# Display.net
KiCad netlist of a schematic drawn in EAGLE
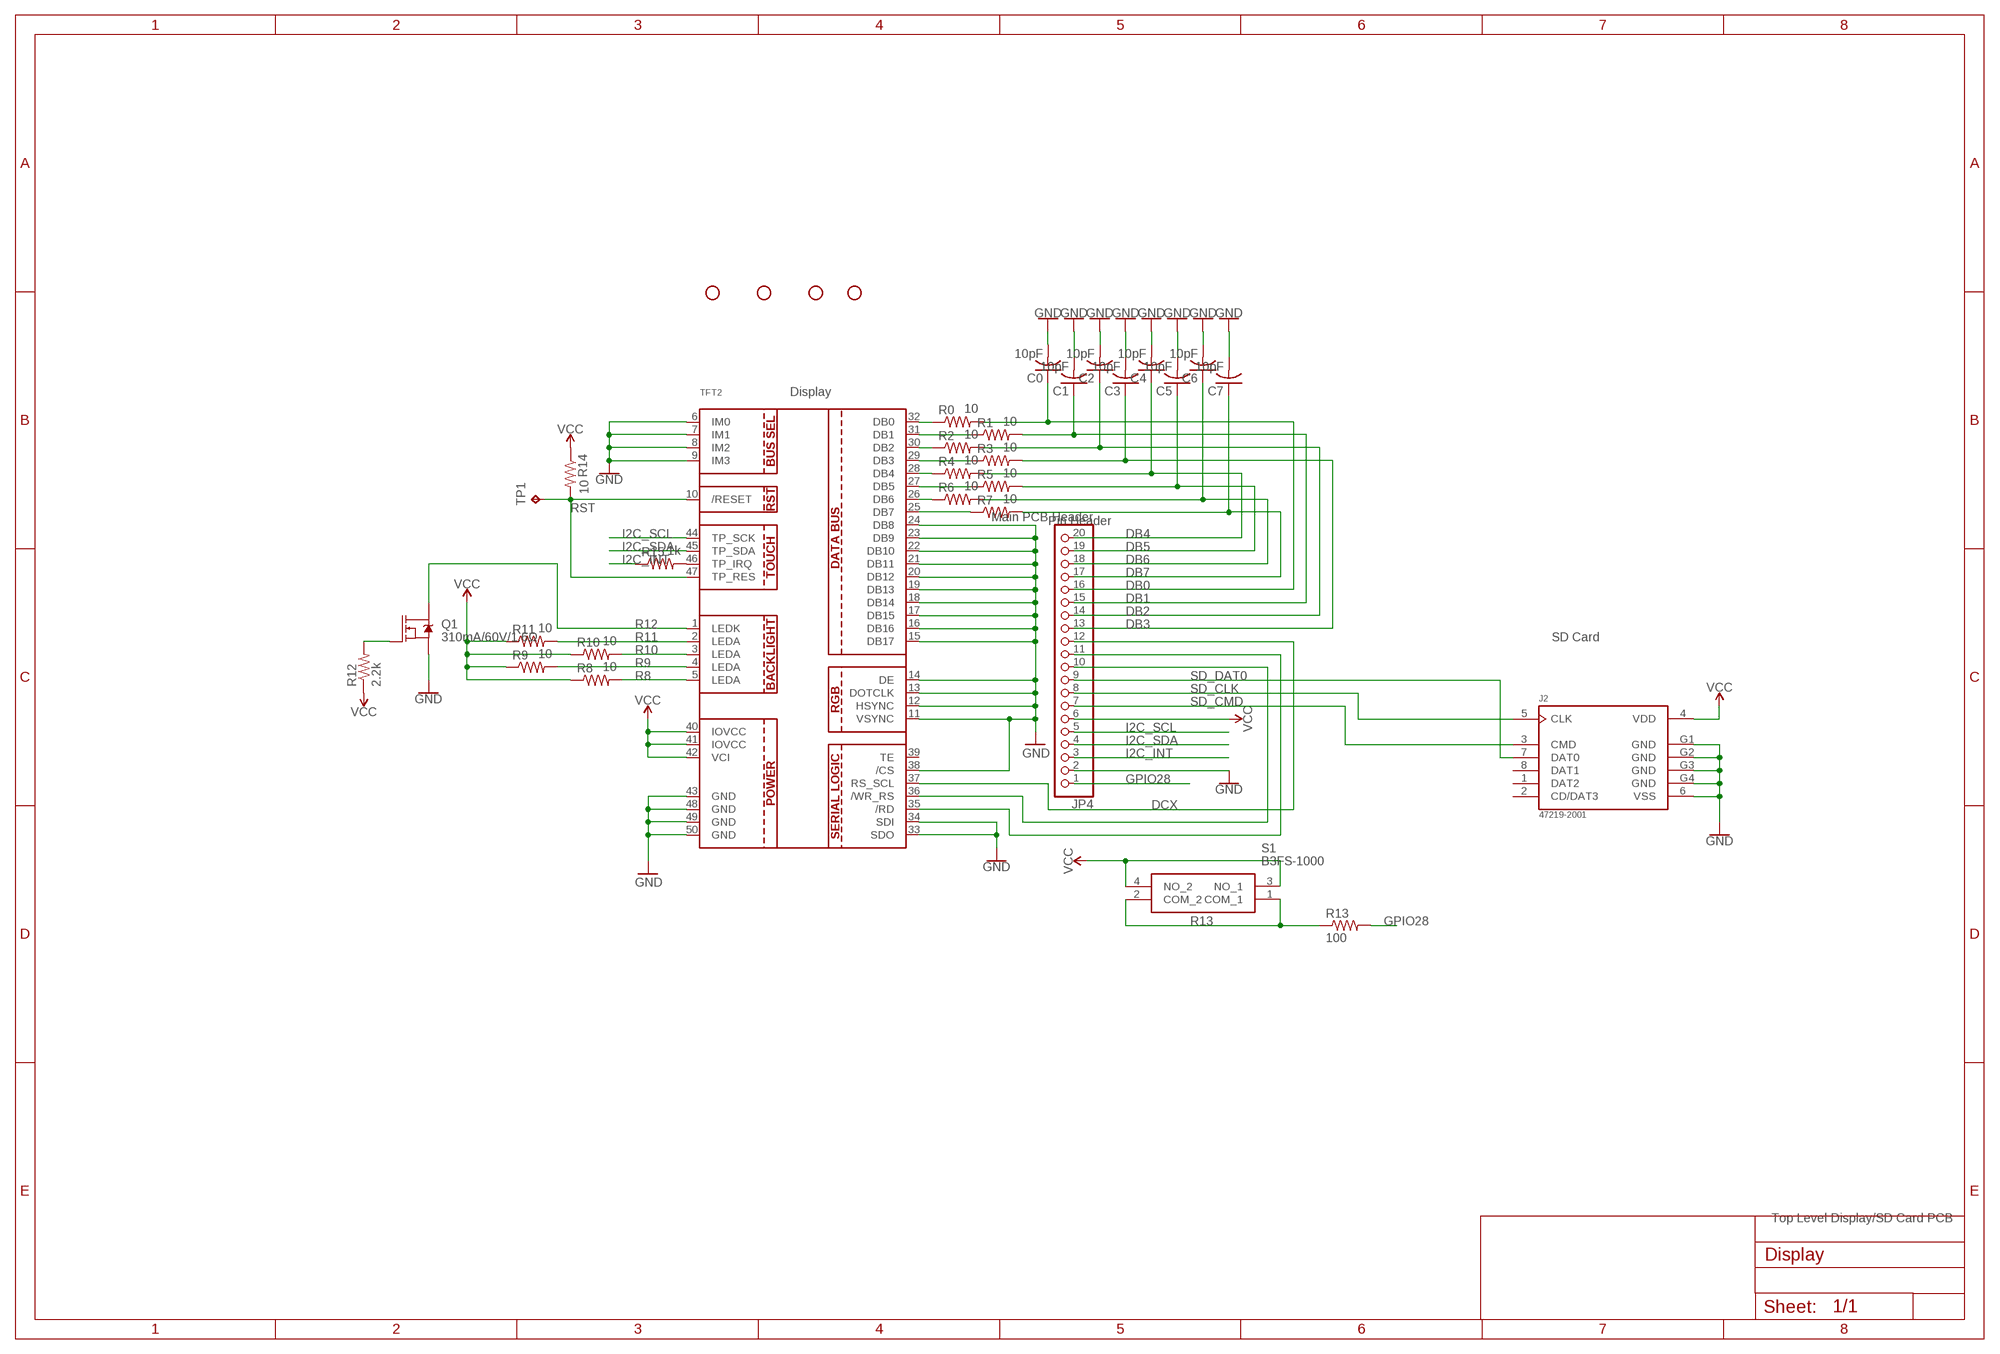
[diagram p0: schematic, sheet 1]

(export (version "E")
  (design (tool "Eeschema 10.0.6"))
  (components
    (comp (ref "C0")
      (value "10pF")
      (footprint "eagle-import:C0805")
      (libsource (lib "eagle-import") (part "C-USC0805"))
    )
    (comp (ref "C1")
      (value "10pF")
      (footprint "eagle-import:C0805")
      (libsource (lib "eagle-import") (part "C-USC0805"))
    )
    (comp (ref "C2")
      (value "10pF")
      (footprint "eagle-import:C0805")
      (libsource (lib "eagle-import") (part "C-USC0805"))
    )
    (comp (ref "C3")
      (value "10pF")
      (footprint "eagle-import:C0805")
      (libsource (lib "eagle-import") (part "C-USC0805"))
    )
    (comp (ref "C4")
      (value "10pF")
      (footprint "eagle-import:C0805")
      (libsource (lib "eagle-import") (part "C-USC0805"))
    )
    (comp (ref "C5")
      (value "10pF")
      (footprint "eagle-import:C0805")
      (libsource (lib "eagle-import") (part "C-USC0805"))
    )
    (comp (ref "C6")
      (value "10pF")
      (footprint "eagle-import:C0805")
      (libsource (lib "eagle-import") (part "C-USC0805"))
    )
    (comp (ref "C7")
      (value "10pF")
      (footprint "eagle-import:C0805")
      (libsource (lib "eagle-import") (part "C-USC0805"))
    )
    (comp (ref "H1")
      (value "STAND-OFF")
      (footprint "eagle-import:STAND-OFF")
      (libsource (lib "eagle-import") (part "STAND-OFF"))
    )
    (comp (ref "H2")
      (value "STAND-OFF")
      (footprint "eagle-import:STAND-OFF")
      (libsource (lib "eagle-import") (part "STAND-OFF"))
    )
    (comp (ref "H3")
      (value "STAND-OFF")
      (footprint "eagle-import:STAND-OFF")
      (libsource (lib "eagle-import") (part "STAND-OFF"))
    )
    (comp (ref "H4")
      (value "STAND-OFF")
      (footprint "eagle-import:STAND-OFF")
      (libsource (lib "eagle-import") (part "STAND-OFF"))
    )
    (comp (ref "J2")
      (value "47219-2001")
      (footprint "eagle-import:MOLEX_47219-2001")
      (fields (field (name "MF") "Molex"))
      (libsource (lib "eagle-import") (part "47219-2001"))
    )
    (comp (ref "JP4")
      (value "Main PCB Header")
      (footprint "eagle-import:1X20")
      (libsource (lib "eagle-import") (part "PINHD-1X20"))
    )
    (comp (ref "Q1")
      (value "310mA/60V/1.6Ω")
      (footprint "eagle-import:SOT323")
      (libsource (lib "eagle-import") (part "MOSFET-NCH-2N7002PW"))
    )
    (comp (ref "R0")
      (value "10")
      (footprint "eagle-import:R0805")
      (libsource (lib "eagle-import") (part "R-US_R0805"))
    )
    (comp (ref "R1")
      (value "10")
      (footprint "eagle-import:R0805")
      (libsource (lib "eagle-import") (part "R-US_R0805"))
    )
    (comp (ref "R2")
      (value "10")
      (footprint "eagle-import:R0805")
      (libsource (lib "eagle-import") (part "R-US_R0805"))
    )
    (comp (ref "R3")
      (value "10")
      (footprint "eagle-import:R0805")
      (libsource (lib "eagle-import") (part "R-US_R0805"))
    )
    (comp (ref "R4")
      (value "10")
      (footprint "eagle-import:R0805")
      (libsource (lib "eagle-import") (part "R-US_R0805"))
    )
    (comp (ref "R5")
      (value "10")
      (footprint "eagle-import:R0805")
      (libsource (lib "eagle-import") (part "R-US_R0805"))
    )
    (comp (ref "R6")
      (value "10")
      (footprint "eagle-import:R0805")
      (libsource (lib "eagle-import") (part "R-US_R0805"))
    )
    (comp (ref "R7")
      (value "10")
      (footprint "eagle-import:R0805")
      (libsource (lib "eagle-import") (part "R-US_R0805"))
    )
    (comp (ref "R8")
      (value "10")
      (footprint "eagle-import:R0805")
      (libsource (lib "eagle-import") (part "R-US_R0805"))
    )
    (comp (ref "R9")
      (value "10")
      (footprint "eagle-import:R0805")
      (libsource (lib "eagle-import") (part "R-US_R0805"))
    )
    (comp (ref "R10")
      (value "10")
      (footprint "eagle-import:R0805")
      (libsource (lib "eagle-import") (part "R-US_R0805"))
    )
    (comp (ref "R11")
      (value "10")
      (footprint "eagle-import:R0805")
      (libsource (lib "eagle-import") (part "R-US_R0805"))
    )
    (comp (ref "R12")
      (value "2.2k")
      (footprint "eagle-import:M0805")
      (libsource (lib "eagle-import") (part "rcl_334_R-US_M0805"))
    )
    (comp (ref "R13")
      (value "100")
      (footprint "eagle-import:R0805")
      (libsource (lib "eagle-import") (part "R-US_R0805"))
    )
    (comp (ref "R14")
      (value "10")
      (footprint "eagle-import:R0805")
      (libsource (lib "eagle-import") (part "R-US_R0805"))
    )
    (comp (ref "R15")
      (value "1k")
      (footprint "eagle-import:R0805")
      (libsource (lib "eagle-import") (part "R-US_R0805"))
    )
    (comp (ref "S1")
      (value "B3FS-1000")
      (footprint "eagle-import:B3FS1000")
      (fields (field (name "MOUSER_PART_NUMBER") "653-B3FS-1000"))
      (libsource (lib "eagle-import") (part "B3FS-1000"))
    )
    (comp (ref "TFT2")
      (value "DISP_LCD_CTP28_DATASHEET")
      (footprint "eagle-import:TFT_CTP28")
      (libsource (lib "eagle-import") (part "DISP_LCD_CTP28_DATASHEET"))
    )
    (comp (ref "TP1")
      (value "TPTP09R")
      (footprint "eagle-import:TP09R")
      (libsource (lib "eagle-import") (part "TPTP09R"))
    )
  )
  (nets
    (net (code "1") (name "/DB0") (class "Default")
      (node (ref "C0") (pin "1") (pinfunction "1_1") (pintype "passive"))
      (node (ref "JP4") (pin "16") (pinfunction "16_16") (pintype "passive"))
      (node (ref "R0") (pin "2") (pinfunction "2_2") (pintype "passive"))
    )
    (net (code "2") (name "/DB1") (class "Default")
      (node (ref "C1") (pin "1") (pinfunction "1_1") (pintype "passive"))
      (node (ref "JP4") (pin "15") (pinfunction "15_15") (pintype "passive"))
      (node (ref "R1") (pin "2") (pinfunction "2_2") (pintype "passive"))
    )
    (net (code "3") (name "/DB2") (class "Default")
      (node (ref "C2") (pin "1") (pinfunction "1_1") (pintype "passive"))
      (node (ref "JP4") (pin "14") (pinfunction "14_14") (pintype "passive"))
      (node (ref "R2") (pin "2") (pinfunction "2_2") (pintype "passive"))
    )
    (net (code "4") (name "/DB3") (class "Default")
      (node (ref "C3") (pin "1") (pinfunction "1_1") (pintype "passive"))
      (node (ref "JP4") (pin "13") (pinfunction "13_13") (pintype "passive"))
      (node (ref "R3") (pin "2") (pinfunction "2_2") (pintype "passive"))
    )
    (net (code "5") (name "/DB4") (class "Default")
      (node (ref "C4") (pin "1") (pinfunction "1_1") (pintype "passive"))
      (node (ref "JP4") (pin "20") (pinfunction "20_20") (pintype "passive"))
      (node (ref "R4") (pin "2") (pinfunction "2_2") (pintype "passive"))
    )
    (net (code "6") (name "/DB5") (class "Default")
      (node (ref "C5") (pin "1") (pinfunction "1_1") (pintype "passive"))
      (node (ref "JP4") (pin "19") (pinfunction "19_19") (pintype "passive"))
      (node (ref "R5") (pin "2") (pinfunction "2_2") (pintype "passive"))
    )
    (net (code "7") (name "/DB6") (class "Default")
      (node (ref "C6") (pin "1") (pinfunction "1_1") (pintype "passive"))
      (node (ref "JP4") (pin "18") (pinfunction "18_18") (pintype "passive"))
      (node (ref "R6") (pin "2") (pinfunction "2_2") (pintype "passive"))
    )
    (net (code "8") (name "/DB7") (class "Default")
      (node (ref "C7") (pin "1") (pinfunction "1_1") (pintype "passive"))
      (node (ref "JP4") (pin "17") (pinfunction "17_17") (pintype "passive"))
      (node (ref "R7") (pin "2") (pinfunction "2_2") (pintype "passive"))
    )
    (net (code "9") (name "/DCX") (class "Default")
      (node (ref "JP4") (pin "12") (pinfunction "12_12") (pintype "passive"))
      (node (ref "TFT2") (pin "37") (pinfunction "RS_SCL_37") (pintype "bidirectional"))
    )
    (net (code "10") (name "/GPIO28") (class "Default")
      (node (ref "JP4") (pin "1") (pinfunction "1_1") (pintype "passive"))
      (node (ref "R13") (pin "2") (pinfunction "2_2") (pintype "passive"))
    )
    (net (code "11") (name "/I2C_INT") (class "Default")
      (node (ref "JP4") (pin "3") (pinfunction "3_3") (pintype "passive"))
      (node (ref "R15") (pin "1") (pinfunction "1_1") (pintype "passive"))
    )
    (net (code "12") (name "/I2C_SCL") (class "Default")
      (node (ref "JP4") (pin "5") (pinfunction "5_5") (pintype "passive"))
      (node (ref "TFT2") (pin "44") (pinfunction "TP_SCK_44") (pintype "bidirectional"))
    )
    (net (code "13") (name "/I2C_SDA") (class "Default")
      (node (ref "JP4") (pin "4") (pinfunction "4_4") (pintype "passive"))
      (node (ref "TFT2") (pin "45") (pinfunction "TP_SDA_45") (pintype "bidirectional"))
    )
    (net (code "14") (name "/R8") (class "Default")
      (node (ref "R8") (pin "2") (pinfunction "2_2") (pintype "passive"))
      (node (ref "TFT2") (pin "5") (pinfunction "LEDA_5") (pintype "bidirectional"))
    )
    (net (code "15") (name "/R9") (class "Default")
      (node (ref "R9") (pin "2") (pinfunction "2_2") (pintype "passive"))
      (node (ref "TFT2") (pin "4") (pinfunction "LEDA_4") (pintype "bidirectional"))
    )
    (net (code "16") (name "/R10") (class "Default")
      (node (ref "R10") (pin "2") (pinfunction "2_2") (pintype "passive"))
      (node (ref "TFT2") (pin "3") (pinfunction "LEDA_3") (pintype "bidirectional"))
    )
    (net (code "17") (name "/R11") (class "Default")
      (node (ref "R11") (pin "2") (pinfunction "2_2") (pintype "passive"))
      (node (ref "TFT2") (pin "2") (pinfunction "LEDA_2") (pintype "bidirectional"))
    )
    (net (code "18") (name "/R12") (class "Default")
      (node (ref "Q1") (pin "3") (pinfunction "D_3") (pintype "bidirectional"))
      (node (ref "TFT2") (pin "1") (pinfunction "LEDK_1") (pintype "bidirectional"))
    )
    (net (code "19") (name "/R13") (class "Default")
      (node (ref "R13") (pin "1") (pinfunction "1_1") (pintype "passive"))
      (node (ref "S1") (pin "1") (pinfunction "COM_1_1") (pintype "bidirectional"))
      (node (ref "S1") (pin "2") (pinfunction "COM_2_2") (pintype "bidirectional"))
    )
    (net (code "20") (name "/RST") (class "Default")
      (node (ref "R14") (pin "2") (pinfunction "2_2") (pintype "passive"))
      (node (ref "TFT2") (pin "10") (pinfunction "/RESET_10") (pintype "bidirectional"))
      (node (ref "TFT2") (pin "47") (pinfunction "TP_RES_47") (pintype "bidirectional"))
      (node (ref "TP1") (pin "TP") (pinfunction "TP_TP") (pintype "input"))
    )
    (net (code "21") (name "/SD_CLK") (class "Default")
      (node (ref "J2") (pin "5") (pinfunction "CLK_5") (pintype "input"))
      (node (ref "JP4") (pin "8") (pinfunction "8_8") (pintype "passive"))
    )
    (net (code "22") (name "/SD_CMD") (class "Default")
      (node (ref "J2") (pin "3") (pinfunction "CMD_3") (pintype "bidirectional"))
      (node (ref "JP4") (pin "7") (pinfunction "7_7") (pintype "passive"))
    )
    (net (code "23") (name "/SD_DAT0") (class "Default")
      (node (ref "J2") (pin "7") (pinfunction "DAT0_7") (pintype "bidirectional"))
      (node (ref "JP4") (pin "9") (pinfunction "9_9") (pintype "passive"))
    )
    (net (code "24") (name "GND") (class "Default")
      (node (ref "C0") (pin "2") (pinfunction "2_2") (pintype "passive"))
      (node (ref "C1") (pin "2") (pinfunction "2_2") (pintype "passive"))
      (node (ref "C2") (pin "2") (pinfunction "2_2") (pintype "passive"))
      (node (ref "C3") (pin "2") (pinfunction "2_2") (pintype "passive"))
      (node (ref "C4") (pin "2") (pinfunction "2_2") (pintype "passive"))
      (node (ref "C5") (pin "2") (pinfunction "2_2") (pintype "passive"))
      (node (ref "C6") (pin "2") (pinfunction "2_2") (pintype "passive"))
      (node (ref "C7") (pin "2") (pinfunction "2_2") (pintype "passive"))
      (node (ref "J2") (pin "6") (pinfunction "VSS_6") (pintype "power_in"))
      (node (ref "J2") (pin "G1") (pinfunction "GND_G1") (pintype "power_in"))
      (node (ref "J2") (pin "G2") (pinfunction "GND_G2") (pintype "power_in"))
      (node (ref "J2") (pin "G3") (pinfunction "GND_G3") (pintype "power_in"))
      (node (ref "J2") (pin "G4") (pinfunction "GND_G4") (pintype "power_in"))
      (node (ref "JP4") (pin "2") (pinfunction "2_2") (pintype "passive"))
      (node (ref "Q1") (pin "2") (pinfunction "S_2") (pintype "bidirectional"))
      (node (ref "TFT2") (pin "11") (pinfunction "VSYNC_11") (pintype "bidirectional"))
      (node (ref "TFT2") (pin "12") (pinfunction "HSYNC_12") (pintype "bidirectional"))
      (node (ref "TFT2") (pin "13") (pinfunction "DOTCLK_13") (pintype "bidirectional"))
      (node (ref "TFT2") (pin "14") (pinfunction "DE_14") (pintype "bidirectional"))
      (node (ref "TFT2") (pin "15") (pinfunction "DB17_15") (pintype "bidirectional"))
      (node (ref "TFT2") (pin "16") (pinfunction "DB16_16") (pintype "bidirectional"))
      (node (ref "TFT2") (pin "17") (pinfunction "DB15_17") (pintype "bidirectional"))
      (node (ref "TFT2") (pin "18") (pinfunction "DB14_18") (pintype "bidirectional"))
      (node (ref "TFT2") (pin "19") (pinfunction "DB13_19") (pintype "bidirectional"))
      (node (ref "TFT2") (pin "20") (pinfunction "DB12_20") (pintype "bidirectional"))
      (node (ref "TFT2") (pin "21") (pinfunction "DB11_21") (pintype "bidirectional"))
      (node (ref "TFT2") (pin "22") (pinfunction "DB10_22") (pintype "bidirectional"))
      (node (ref "TFT2") (pin "23") (pinfunction "DB9_23") (pintype "bidirectional"))
      (node (ref "TFT2") (pin "24") (pinfunction "DB8_24") (pintype "bidirectional"))
      (node (ref "TFT2") (pin "33") (pinfunction "SDO_33") (pintype "bidirectional"))
      (node (ref "TFT2") (pin "34") (pinfunction "SDI_34") (pintype "bidirectional"))
      (node (ref "TFT2") (pin "38") (pinfunction "/CS_38") (pintype "bidirectional"))
      (node (ref "TFT2") (pin "43") (pinfunction "GND_43") (pintype "bidirectional"))
      (node (ref "TFT2") (pin "48") (pinfunction "GND_48") (pintype "bidirectional"))
      (node (ref "TFT2") (pin "49") (pinfunction "GND_49") (pintype "bidirectional"))
      (node (ref "TFT2") (pin "50") (pinfunction "GND_50") (pintype "bidirectional"))
      (node (ref "TFT2") (pin "6") (pinfunction "IM0_6") (pintype "bidirectional"))
      (node (ref "TFT2") (pin "7") (pinfunction "IM1_7") (pintype "bidirectional"))
      (node (ref "TFT2") (pin "8") (pinfunction "IM2_8") (pintype "bidirectional"))
      (node (ref "TFT2") (pin "9") (pinfunction "IM3_9") (pintype "bidirectional"))
    )
    (net (code "25") (name "Net-(Q1-G)") (class "Default")
      (node (ref "Q1") (pin "1") (pinfunction "G_1") (pintype "bidirectional"))
      (node (ref "R12") (pin "2") (pinfunction "2_2") (pintype "passive"))
    )
    (net (code "26") (name "Net-(TFT2-DB0)") (class "Default")
      (node (ref "R0") (pin "1") (pinfunction "1_1") (pintype "passive"))
      (node (ref "TFT2") (pin "32") (pinfunction "DB0_32") (pintype "bidirectional"))
    )
    (net (code "27") (name "Net-(TFT2-DB1)") (class "Default")
      (node (ref "R1") (pin "1") (pinfunction "1_1") (pintype "passive"))
      (node (ref "TFT2") (pin "31") (pinfunction "DB1_31") (pintype "bidirectional"))
    )
    (net (code "28") (name "Net-(TFT2-DB2)") (class "Default")
      (node (ref "R2") (pin "1") (pinfunction "1_1") (pintype "passive"))
      (node (ref "TFT2") (pin "30") (pinfunction "DB2_30") (pintype "bidirectional"))
    )
    (net (code "29") (name "Net-(TFT2-DB3)") (class "Default")
      (node (ref "R3") (pin "1") (pinfunction "1_1") (pintype "passive"))
      (node (ref "TFT2") (pin "29") (pinfunction "DB3_29") (pintype "bidirectional"))
    )
    (net (code "30") (name "Net-(TFT2-DB4)") (class "Default")
      (node (ref "R4") (pin "1") (pinfunction "1_1") (pintype "passive"))
      (node (ref "TFT2") (pin "28") (pinfunction "DB4_28") (pintype "bidirectional"))
    )
    (net (code "31") (name "Net-(TFT2-DB5)") (class "Default")
      (node (ref "R5") (pin "1") (pinfunction "1_1") (pintype "passive"))
      (node (ref "TFT2") (pin "27") (pinfunction "DB5_27") (pintype "bidirectional"))
    )
    (net (code "32") (name "Net-(TFT2-DB6)") (class "Default")
      (node (ref "R6") (pin "1") (pinfunction "1_1") (pintype "passive"))
      (node (ref "TFT2") (pin "26") (pinfunction "DB6_26") (pintype "bidirectional"))
    )
    (net (code "33") (name "Net-(TFT2-DB7)") (class "Default")
      (node (ref "R7") (pin "1") (pinfunction "1_1") (pintype "passive"))
      (node (ref "TFT2") (pin "25") (pinfunction "DB7_25") (pintype "bidirectional"))
    )
    (net (code "34") (name "Net-(TFT2-TP_IRQ)") (class "Default")
      (node (ref "R15") (pin "2") (pinfunction "2_2") (pintype "passive"))
      (node (ref "TFT2") (pin "46") (pinfunction "TP_IRQ_46") (pintype "bidirectional"))
    )
    (net (code "35") (name "Net-(TFT2-{slash}RD)") (class "Default")
      (node (ref "JP4") (pin "11") (pinfunction "11_11") (pintype "passive"))
      (node (ref "TFT2") (pin "35") (pinfunction "/RD_35") (pintype "bidirectional"))
    )
    (net (code "36") (name "Net-(TFT2-{slash}WR_RS)") (class "Default")
      (node (ref "JP4") (pin "10") (pinfunction "10_10") (pintype "passive"))
      (node (ref "TFT2") (pin "36") (pinfunction "/WR_RS_36") (pintype "bidirectional"))
    )
    (net (code "37") (name "VCC") (class "Default")
      (node (ref "J2") (pin "4") (pinfunction "VDD_4") (pintype "power_in"))
      (node (ref "JP4") (pin "6") (pinfunction "6_6") (pintype "passive"))
      (node (ref "R10") (pin "1") (pinfunction "1_1") (pintype "passive"))
      (node (ref "R11") (pin "1") (pinfunction "1_1") (pintype "passive"))
      (node (ref "R12") (pin "1") (pinfunction "1_1") (pintype "passive"))
      (node (ref "R14") (pin "1") (pinfunction "1_1") (pintype "passive"))
      (node (ref "R8") (pin "1") (pinfunction "1_1") (pintype "passive"))
      (node (ref "R9") (pin "1") (pinfunction "1_1") (pintype "passive"))
      (node (ref "S1") (pin "3") (pinfunction "NO_1_3") (pintype "bidirectional"))
      (node (ref "S1") (pin "4") (pinfunction "NO_2_4") (pintype "bidirectional"))
      (node (ref "TFT2") (pin "40") (pinfunction "IOVCC_40") (pintype "bidirectional"))
      (node (ref "TFT2") (pin "41") (pinfunction "IOVCC_41") (pintype "bidirectional"))
      (node (ref "TFT2") (pin "42") (pinfunction "VCI_42") (pintype "bidirectional"))
    )
    (net (code "38") (name "unconnected-(J2-CD{slash}DAT3-Pad2)") (class "Default")
      (node (ref "J2") (pin "2") (pinfunction "CD/DAT3_2") (pintype "bidirectional"))
    )
    (net (code "39") (name "unconnected-(J2-DAT1-Pad8)") (class "Default")
      (node (ref "J2") (pin "8") (pinfunction "DAT1_8") (pintype "bidirectional"))
    )
    (net (code "40") (name "unconnected-(J2-DAT2-Pad1)") (class "Default")
      (node (ref "J2") (pin "1") (pinfunction "DAT2_1") (pintype "bidirectional"))
    )
    (net (code "41") (name "unconnected-(TFT2-TE-Pad39)") (class "Default")
      (node (ref "TFT2") (pin "39") (pinfunction "TE_39") (pintype "bidirectional"))
    )
  )
)
